# Fri3D_IRA_Peripherals.net
KiCad netlist of a schematic drawn in Altium Designer
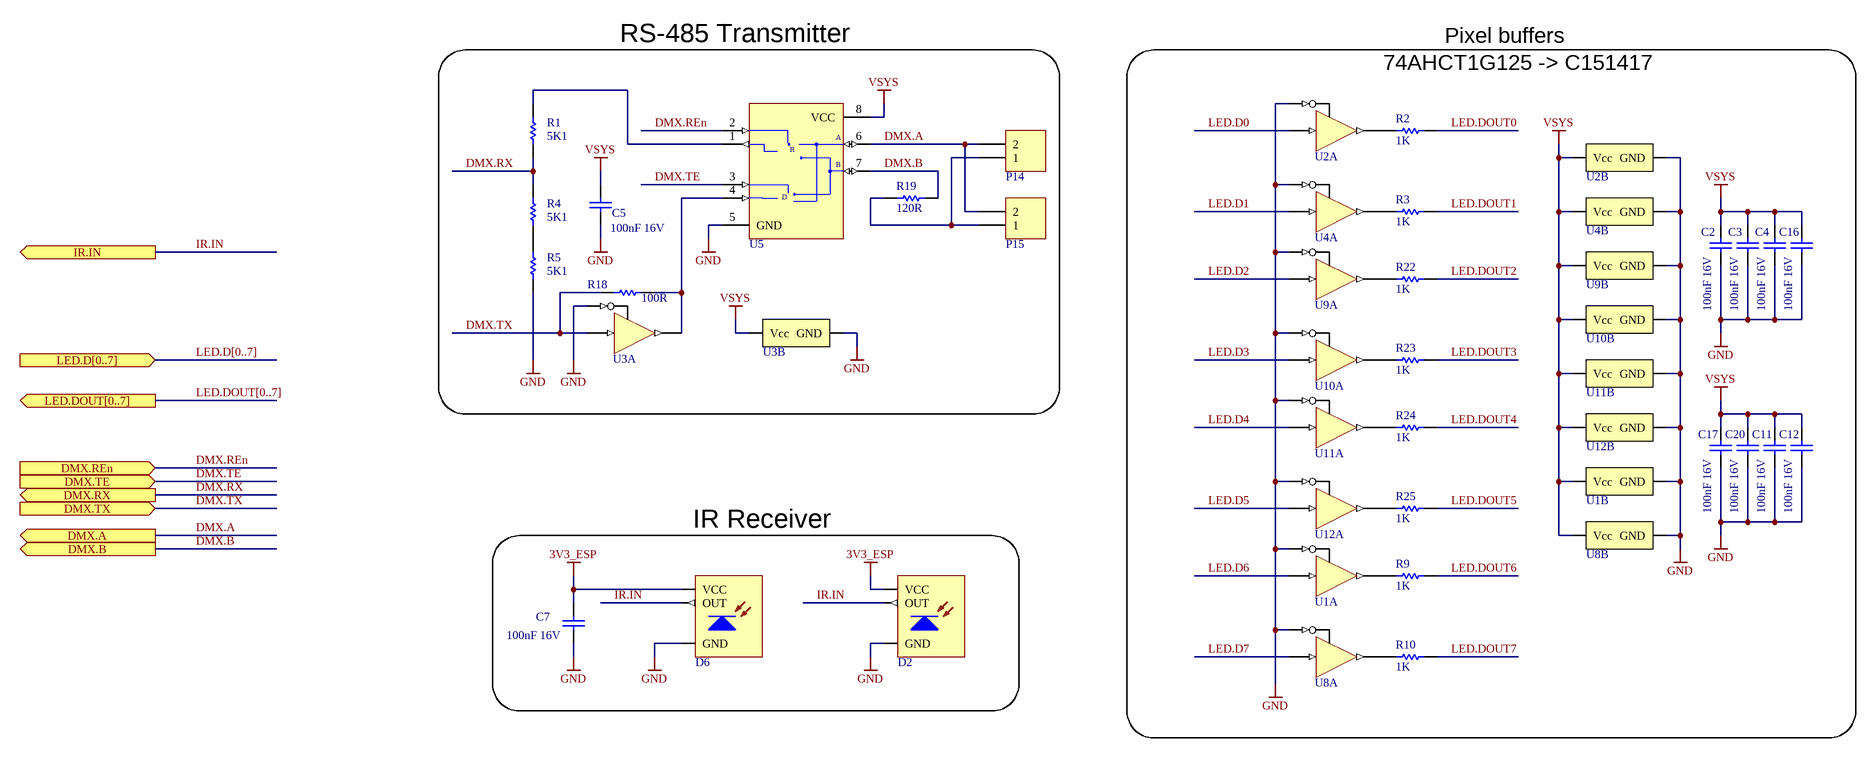
[diagram p0: Fri3D_IRA_Peripherals.SchDoc]

(export (version "E")
  (design (tool "Eeschema 10.0.6"))
  (components
    (comp (ref "C2")
      (value "100nF 16V")
      (footprint "C0603_N")
      (description "Capacitor Ceramic")
      (libsource (lib "Phyx_Components") (part "CAP_CERAMIC"))
    )
    (comp (ref "C3")
      (value "100nF 16V")
      (footprint "C0603_N")
      (description "Capacitor Ceramic")
      (libsource (lib "Phyx_Components") (part "CAP_CERAMIC"))
    )
    (comp (ref "C4")
      (value "100nF 16V")
      (footprint "C0603_N")
      (description "Capacitor Ceramic")
      (libsource (lib "Phyx_Components") (part "CAP_CERAMIC"))
    )
    (comp (ref "C5")
      (value "100nF 16V")
      (footprint "C0603_N")
      (description "Capacitor Ceramic")
      (libsource (lib "Phyx_Components") (part "CAP_CERAMIC"))
    )
    (comp (ref "C7")
      (value "100nF 16V")
      (footprint "C0603_N")
      (description "Capacitor Ceramic")
      (libsource (lib "Phyx_Components") (part "CAP_CERAMIC"))
    )
    (comp (ref "C11")
      (value "100nF 16V")
      (footprint "C0603_N")
      (description "Capacitor Ceramic")
      (libsource (lib "Phyx_Components") (part "CAP_CERAMIC"))
    )
    (comp (ref "C12")
      (value "100nF 16V")
      (footprint "C0603_N")
      (description "Capacitor Ceramic")
      (libsource (lib "Phyx_Components") (part "CAP_CERAMIC"))
    )
    (comp (ref "C16")
      (value "100nF 16V")
      (footprint "C0603_N")
      (description "Capacitor Ceramic")
      (libsource (lib "Phyx_Components") (part "CAP_CERAMIC"))
    )
    (comp (ref "C17")
      (value "100nF 16V")
      (footprint "C0603_N")
      (description "Capacitor Ceramic")
      (libsource (lib "Phyx_Components") (part "CAP_CERAMIC"))
    )
    (comp (ref "C20")
      (value "100nF 16V")
      (footprint "C0603_N")
      (description "Capacitor Ceramic")
      (libsource (lib "Phyx_Components") (part "CAP_CERAMIC"))
    )
    (comp (ref "D2")
      (value "ZIRM-5042B-42-Z2 Infrared Receiver 38 kHz 45° 2.7-5.5V 940nm")
      (footprint "CHAU_ZIRM-5042B-42-Z2")
      (description "=Description")
      (libsource (lib "Phyx_Components") (part "PHO_IR_TSOP381x"))
    )
    (comp (ref "D6")
      (value "IRM-3638N3F14 Infrared Receiver 38 kHz 45° 2.7-5.5V")
      (footprint "VIS_TSOP381x_BENT")
      (description "=Description")
      (libsource (lib "Phyx_Components") (part "PHO_IR_TSOP381x"))
    )
    (comp (ref "P14")
      (value "Easy to solder connection")
      (footprint "SOLDER_SW_V_1MM")
      (libsource (lib "Phyx_Components") (part "Header 2"))
    )
    (comp (ref "P15")
      (value "Header 2")
      (footprint "HDR1X2")
      (libsource (lib "Phyx_Components") (part "Header 2"))
    )
    (comp (ref "R1")
      (value "5K1")
      (footprint "R0603_N")
      (libsource (lib "Phyx_Components") (part "RESISTOR"))
    )
    (comp (ref "R2") (value "1K") (footprint "R0603_N") (libsource (lib "Phyx_Components") (part "RESISTOR")))
    (comp (ref "R3") (value "1K") (footprint "R0603_N") (libsource (lib "Phyx_Components") (part "RESISTOR")))
    (comp (ref "R4")
      (value "5K1")
      (footprint "R0603_N")
      (libsource (lib "Phyx_Components") (part "RESISTOR"))
    )
    (comp (ref "R5")
      (value "5K1")
      (footprint "R0603_N")
      (libsource (lib "Phyx_Components") (part "RESISTOR"))
    )
    (comp (ref "R9") (value "1K") (footprint "R0603_N") (libsource (lib "Phyx_Components") (part "RESISTOR")))
    (comp (ref "R10")
      (value "1K")
      (footprint "R0603_N")
      (libsource (lib "Phyx_Components") (part "RESISTOR"))
    )
    (comp (ref "R18")
      (value "100R")
      (footprint "R0603_N")
      (libsource (lib "Phyx_Components") (part "RESISTOR"))
    )
    (comp (ref "R19")
      (value "120R")
      (footprint "R1206")
      (libsource (lib "Phyx_Components") (part "RESISTOR"))
    )
    (comp (ref "R22")
      (value "1K")
      (footprint "R0603_N")
      (libsource (lib "Phyx_Components") (part "RESISTOR"))
    )
    (comp (ref "R23")
      (value "1K")
      (footprint "R0603_N")
      (libsource (lib "Phyx_Components") (part "RESISTOR"))
    )
    (comp (ref "R24")
      (value "1K")
      (footprint "R0603_N")
      (libsource (lib "Phyx_Components") (part "RESISTOR"))
    )
    (comp (ref "R25")
      (value "1K")
      (footprint "R0603_N")
      (libsource (lib "Phyx_Components") (part "RESISTOR"))
    )
    (comp (ref "U1")
      (value "SN74AHCT1G125DCKR  Buffer, Tri-State, 4.5V to 5.5V")
      (footprint "TI_DCK_R-PDSO-G5")
      (description "=Description")
      (libsource (lib "Phyx_Components") (part "SN74AHCT1G125"))
    )
    (comp (ref "U2")
      (value "SN74AHCT1G125DCKR  Buffer, Tri-State, 4.5V to 5.5V")
      (footprint "TI_DCK_R-PDSO-G5")
      (description "=Description")
      (libsource (lib "Phyx_Components") (part "SN74AHCT1G125"))
    )
    (comp (ref "U3")
      (value "SN74AHCT1G125DCKR  Buffer, Tri-State, 4.5V to 5.5V")
      (footprint "TI_DCK_R-PDSO-G5")
      (description "=Description")
      (libsource (lib "Phyx_Components") (part "SN74AHCT1G125"))
    )
    (comp (ref "U4")
      (value "SN74AHCT1G125DCKR  Buffer, Tri-State, 4.5V to 5.5V")
      (footprint "TI_DCK_R-PDSO-G5")
      (description "=Description")
      (libsource (lib "Phyx_Components") (part "SN74AHCT1G125"))
    )
    (comp (ref "U5")
      (value "RS-485 5V Transceiver 500kbps")
      (footprint "SOIC_N_8")
      (description "WS3085 # RS-485 transceiver")
      (libsource (lib "Phyx_Components") (part "MAX485"))
    )
    (comp (ref "U8")
      (value "SN74AHCT1G125DCKR  Buffer, Tri-State, 4.5V to 5.5V")
      (footprint "TI_DCK_R-PDSO-G5")
      (description "=Description")
      (libsource (lib "Phyx_Components") (part "SN74AHCT1G125"))
    )
    (comp (ref "U9")
      (value "SN74AHCT1G125DCKR  Buffer, Tri-State, 4.5V to 5.5V")
      (footprint "TI_DCK_R-PDSO-G5")
      (description "=Description")
      (libsource (lib "Phyx_Components") (part "SN74AHCT1G125"))
    )
    (comp (ref "U10")
      (value "SN74AHCT1G125DCKR  Buffer, Tri-State, 4.5V to 5.5V")
      (footprint "TI_DCK_R-PDSO-G5")
      (description "=Description")
      (libsource (lib "Phyx_Components") (part "SN74AHCT1G125"))
    )
    (comp (ref "U11")
      (value "SN74AHCT1G125DCKR  Buffer, Tri-State, 4.5V to 5.5V")
      (footprint "TI_DCK_R-PDSO-G5")
      (description "=Description")
      (libsource (lib "Phyx_Components") (part "SN74AHCT1G125"))
    )
    (comp (ref "U12")
      (value "SN74AHCT1G125DCKR  Buffer, Tri-State, 4.5V to 5.5V")
      (footprint "TI_DCK_R-PDSO-G5")
      (description "=Description")
      (libsource (lib "Phyx_Components") (part "SN74AHCT1G125"))
    )
  )
  (nets
    (net (code "1") (name "/DMX.A") (class "Default")
      (node (ref "P14") (pin "2") (pinfunction "2_2") (pintype "passive"))
      (node (ref "P15") (pin "2") (pinfunction "2_2") (pintype "passive"))
      (node (ref "U5") (pin "6") (pinfunction "A_6") (pintype "bidirectional"))
    )
    (net (code "2") (name "/DMX.B") (class "Default")
      (node (ref "R19") (pin "2") (pinfunction "2_2") (pintype "passive"))
      (node (ref "U5") (pin "7") (pinfunction "B_7") (pintype "bidirectional"))
    )
    (net (code "3") (name "/DMX.REn") (class "Default")
      (node (ref "U5") (pin "2") (pinfunction "~{RE}_2") (pintype "input"))
    )
    (net (code "4") (name "/DMX.RX") (class "Default")
      (node (ref "R1") (pin "2") (pinfunction "2_2") (pintype "passive"))
      (node (ref "R4") (pin "1") (pinfunction "1_1") (pintype "passive"))
    )
    (net (code "5") (name "/DMX.TE") (class "Default")
      (node (ref "U5") (pin "3") (pinfunction "DE_3") (pintype "input"))
    )
    (net (code "6") (name "/DMX.TX") (class "Default")
      (node (ref "R18") (pin "1") (pinfunction "1_1") (pintype "passive"))
      (node (ref "U3") (pin "2") (pinfunction "A_2") (pintype "input"))
    )
    (net (code "7") (name "/IR.IN") (class "Default")
      (node (ref "D2") (pin "1") (pinfunction "OUT_1") (pintype "output"))
      (node (ref "D6") (pin "1") (pinfunction "OUT_1") (pintype "output"))
    )
    (net (code "8") (name "/LED.D0") (class "Default")
      (node (ref "U2") (pin "2") (pinfunction "A_2") (pintype "input"))
    )
    (net (code "9") (name "/LED.D1") (class "Default")
      (node (ref "U4") (pin "2") (pinfunction "A_2") (pintype "input"))
    )
    (net (code "10") (name "/LED.D2") (class "Default")
      (node (ref "U9") (pin "2") (pinfunction "A_2") (pintype "input"))
    )
    (net (code "11") (name "/LED.D3") (class "Default")
      (node (ref "U10") (pin "2") (pinfunction "A_2") (pintype "input"))
    )
    (net (code "12") (name "/LED.D4") (class "Default")
      (node (ref "U11") (pin "2") (pinfunction "A_2") (pintype "input"))
    )
    (net (code "13") (name "/LED.D5") (class "Default")
      (node (ref "U12") (pin "2") (pinfunction "A_2") (pintype "input"))
    )
    (net (code "14") (name "/LED.D6") (class "Default")
      (node (ref "U1") (pin "2") (pinfunction "A_2") (pintype "input"))
    )
    (net (code "15") (name "/LED.D7") (class "Default")
      (node (ref "U8") (pin "2") (pinfunction "A_2") (pintype "input"))
    )
    (net (code "16") (name "/LED.DOUT0") (class "Default")
      (node (ref "R2") (pin "2") (pinfunction "2_2") (pintype "passive"))
    )
    (net (code "17") (name "/LED.DOUT1") (class "Default")
      (node (ref "R3") (pin "2") (pinfunction "2_2") (pintype "passive"))
    )
    (net (code "18") (name "/LED.DOUT2") (class "Default")
      (node (ref "R22") (pin "2") (pinfunction "2_2") (pintype "passive"))
    )
    (net (code "19") (name "/LED.DOUT3") (class "Default")
      (node (ref "R23") (pin "2") (pinfunction "2_2") (pintype "passive"))
    )
    (net (code "20") (name "/LED.DOUT4") (class "Default")
      (node (ref "R24") (pin "2") (pinfunction "2_2") (pintype "passive"))
    )
    (net (code "21") (name "/LED.DOUT5") (class "Default")
      (node (ref "R25") (pin "2") (pinfunction "2_2") (pintype "passive"))
    )
    (net (code "22") (name "/LED.DOUT6") (class "Default")
      (node (ref "R9") (pin "2") (pinfunction "2_2") (pintype "passive"))
    )
    (net (code "23") (name "/LED.DOUT7") (class "Default")
      (node (ref "R10") (pin "2") (pinfunction "2_2") (pintype "passive"))
    )
    (net (code "26") (name "3V3_ESP") (class "Default")
      (node (ref "C7") (pin "1") (pinfunction "1_1") (pintype "passive"))
      (node (ref "D2") (pin "3") (pinfunction "VCC_3") (pintype "power_in"))
      (node (ref "D6") (pin "3") (pinfunction "VCC_3") (pintype "power_in"))
    )
    (net (code "27") (name "GND") (class "Default")
      (node (ref "C11") (pin "2") (pinfunction "2_2") (pintype "passive"))
      (node (ref "C12") (pin "2") (pinfunction "2_2") (pintype "passive"))
      (node (ref "C16") (pin "2") (pinfunction "2_2") (pintype "passive"))
      (node (ref "C17") (pin "2") (pinfunction "2_2") (pintype "passive"))
      (node (ref "C2") (pin "2") (pinfunction "2_2") (pintype "passive"))
      (node (ref "C20") (pin "2") (pinfunction "2_2") (pintype "passive"))
      (node (ref "C3") (pin "2") (pinfunction "2_2") (pintype "passive"))
      (node (ref "C4") (pin "2") (pinfunction "2_2") (pintype "passive"))
      (node (ref "C5") (pin "2") (pinfunction "2_2") (pintype "passive"))
      (node (ref "C7") (pin "2") (pinfunction "2_2") (pintype "passive"))
      (node (ref "D2") (pin "2") (pinfunction "GND_2") (pintype "power_in"))
      (node (ref "D6") (pin "2") (pinfunction "GND_2") (pintype "power_in"))
      (node (ref "R5") (pin "2") (pinfunction "2_2") (pintype "passive"))
      (node (ref "U1") (pin "1") (pinfunction "~{OE}_1") (pintype "input"))
      (node (ref "U1") (pin "3") (pinfunction "GND_3") (pintype "power_in"))
      (node (ref "U10") (pin "1") (pinfunction "~{OE}_1") (pintype "input"))
      (node (ref "U10") (pin "3") (pinfunction "GND_3") (pintype "power_in"))
      (node (ref "U11") (pin "1") (pinfunction "~{OE}_1") (pintype "input"))
      (node (ref "U11") (pin "3") (pinfunction "GND_3") (pintype "power_in"))
      (node (ref "U12") (pin "1") (pinfunction "~{OE}_1") (pintype "input"))
      (node (ref "U12") (pin "3") (pinfunction "GND_3") (pintype "power_in"))
      (node (ref "U2") (pin "1") (pinfunction "~{OE}_1") (pintype "input"))
      (node (ref "U2") (pin "3") (pinfunction "GND_3") (pintype "power_in"))
      (node (ref "U3") (pin "1") (pinfunction "~{OE}_1") (pintype "input"))
      (node (ref "U3") (pin "3") (pinfunction "GND_3") (pintype "power_in"))
      (node (ref "U4") (pin "1") (pinfunction "~{OE}_1") (pintype "input"))
      (node (ref "U4") (pin "3") (pinfunction "GND_3") (pintype "power_in"))
      (node (ref "U5") (pin "5") (pinfunction "GND_5") (pintype "power_in"))
      (node (ref "U8") (pin "1") (pinfunction "~{OE}_1") (pintype "input"))
      (node (ref "U8") (pin "3") (pinfunction "GND_3") (pintype "power_in"))
      (node (ref "U9") (pin "1") (pinfunction "~{OE}_1") (pintype "input"))
      (node (ref "U9") (pin "3") (pinfunction "GND_3") (pintype "power_in"))
    )
    (net (code "28") (name "Net-(P14-Pad1)") (class "Default")
      (node (ref "P14") (pin "1") (pinfunction "1_1") (pintype "passive"))
      (node (ref "P15") (pin "1") (pinfunction "1_1") (pintype "passive"))
      (node (ref "R19") (pin "1") (pinfunction "1_1") (pintype "passive"))
    )
    (net (code "29") (name "Net-(R4-Pad2)") (class "Default")
      (node (ref "R4") (pin "2") (pinfunction "2_2") (pintype "passive"))
      (node (ref "R5") (pin "1") (pinfunction "1_1") (pintype "passive"))
    )
    (net (code "30") (name "Net-(U1A-Y)") (class "Default")
      (node (ref "R9") (pin "1") (pinfunction "1_1") (pintype "passive"))
      (node (ref "U1") (pin "4") (pinfunction "Y_4") (pintype "output"))
    )
    (net (code "31") (name "Net-(U2A-Y)") (class "Default")
      (node (ref "R2") (pin "1") (pinfunction "1_1") (pintype "passive"))
      (node (ref "U2") (pin "4") (pinfunction "Y_4") (pintype "output"))
    )
    (net (code "32") (name "Net-(U3A-Y)") (class "Default")
      (node (ref "R18") (pin "2") (pinfunction "2_2") (pintype "passive"))
      (node (ref "U3") (pin "4") (pinfunction "Y_4") (pintype "output"))
      (node (ref "U5") (pin "4") (pinfunction "DI_4") (pintype "input"))
    )
    (net (code "33") (name "Net-(U4A-Y)") (class "Default")
      (node (ref "R3") (pin "1") (pinfunction "1_1") (pintype "passive"))
      (node (ref "U4") (pin "4") (pinfunction "Y_4") (pintype "output"))
    )
    (net (code "34") (name "Net-(U5-RO)") (class "Default")
      (node (ref "R1") (pin "1") (pinfunction "1_1") (pintype "passive"))
      (node (ref "U5") (pin "1") (pinfunction "RO_1") (pintype "output"))
    )
    (net (code "35") (name "Net-(U8A-Y)") (class "Default")
      (node (ref "R10") (pin "1") (pinfunction "1_1") (pintype "passive"))
      (node (ref "U8") (pin "4") (pinfunction "Y_4") (pintype "output"))
    )
    (net (code "36") (name "Net-(U9A-Y)") (class "Default")
      (node (ref "R22") (pin "1") (pinfunction "1_1") (pintype "passive"))
      (node (ref "U9") (pin "4") (pinfunction "Y_4") (pintype "output"))
    )
    (net (code "37") (name "Net-(U10A-Y)") (class "Default")
      (node (ref "R23") (pin "1") (pinfunction "1_1") (pintype "passive"))
      (node (ref "U10") (pin "4") (pinfunction "Y_4") (pintype "output"))
    )
    (net (code "38") (name "Net-(U11A-Y)") (class "Default")
      (node (ref "R24") (pin "1") (pinfunction "1_1") (pintype "passive"))
      (node (ref "U11") (pin "4") (pinfunction "Y_4") (pintype "output"))
    )
    (net (code "39") (name "Net-(U12A-Y)") (class "Default")
      (node (ref "R25") (pin "1") (pinfunction "1_1") (pintype "passive"))
      (node (ref "U12") (pin "4") (pinfunction "Y_4") (pintype "output"))
    )
    (net (code "40") (name "VSYS") (class "Default")
      (node (ref "C11") (pin "1") (pinfunction "1_1") (pintype "passive"))
      (node (ref "C12") (pin "1") (pinfunction "1_1") (pintype "passive"))
      (node (ref "C16") (pin "1") (pinfunction "1_1") (pintype "passive"))
      (node (ref "C17") (pin "1") (pinfunction "1_1") (pintype "passive"))
      (node (ref "C2") (pin "1") (pinfunction "1_1") (pintype "passive"))
      (node (ref "C20") (pin "1") (pinfunction "1_1") (pintype "passive"))
      (node (ref "C3") (pin "1") (pinfunction "1_1") (pintype "passive"))
      (node (ref "C4") (pin "1") (pinfunction "1_1") (pintype "passive"))
      (node (ref "C5") (pin "1") (pinfunction "1_1") (pintype "passive"))
      (node (ref "U1") (pin "5") (pinfunction "Vcc_5") (pintype "power_in"))
      (node (ref "U10") (pin "5") (pinfunction "Vcc_5") (pintype "power_in"))
      (node (ref "U11") (pin "5") (pinfunction "Vcc_5") (pintype "power_in"))
      (node (ref "U12") (pin "5") (pinfunction "Vcc_5") (pintype "power_in"))
      (node (ref "U2") (pin "5") (pinfunction "Vcc_5") (pintype "power_in"))
      (node (ref "U3") (pin "5") (pinfunction "Vcc_5") (pintype "power_in"))
      (node (ref "U4") (pin "5") (pinfunction "Vcc_5") (pintype "power_in"))
      (node (ref "U5") (pin "8") (pinfunction "VCC_8") (pintype "power_in"))
      (node (ref "U8") (pin "5") (pinfunction "Vcc_5") (pintype "power_in"))
      (node (ref "U9") (pin "5") (pinfunction "Vcc_5") (pintype "power_in"))
    )
  )
)
